# Fri3D_2026_02.net
KiCad netlist of a schematic drawn in Altium Designer
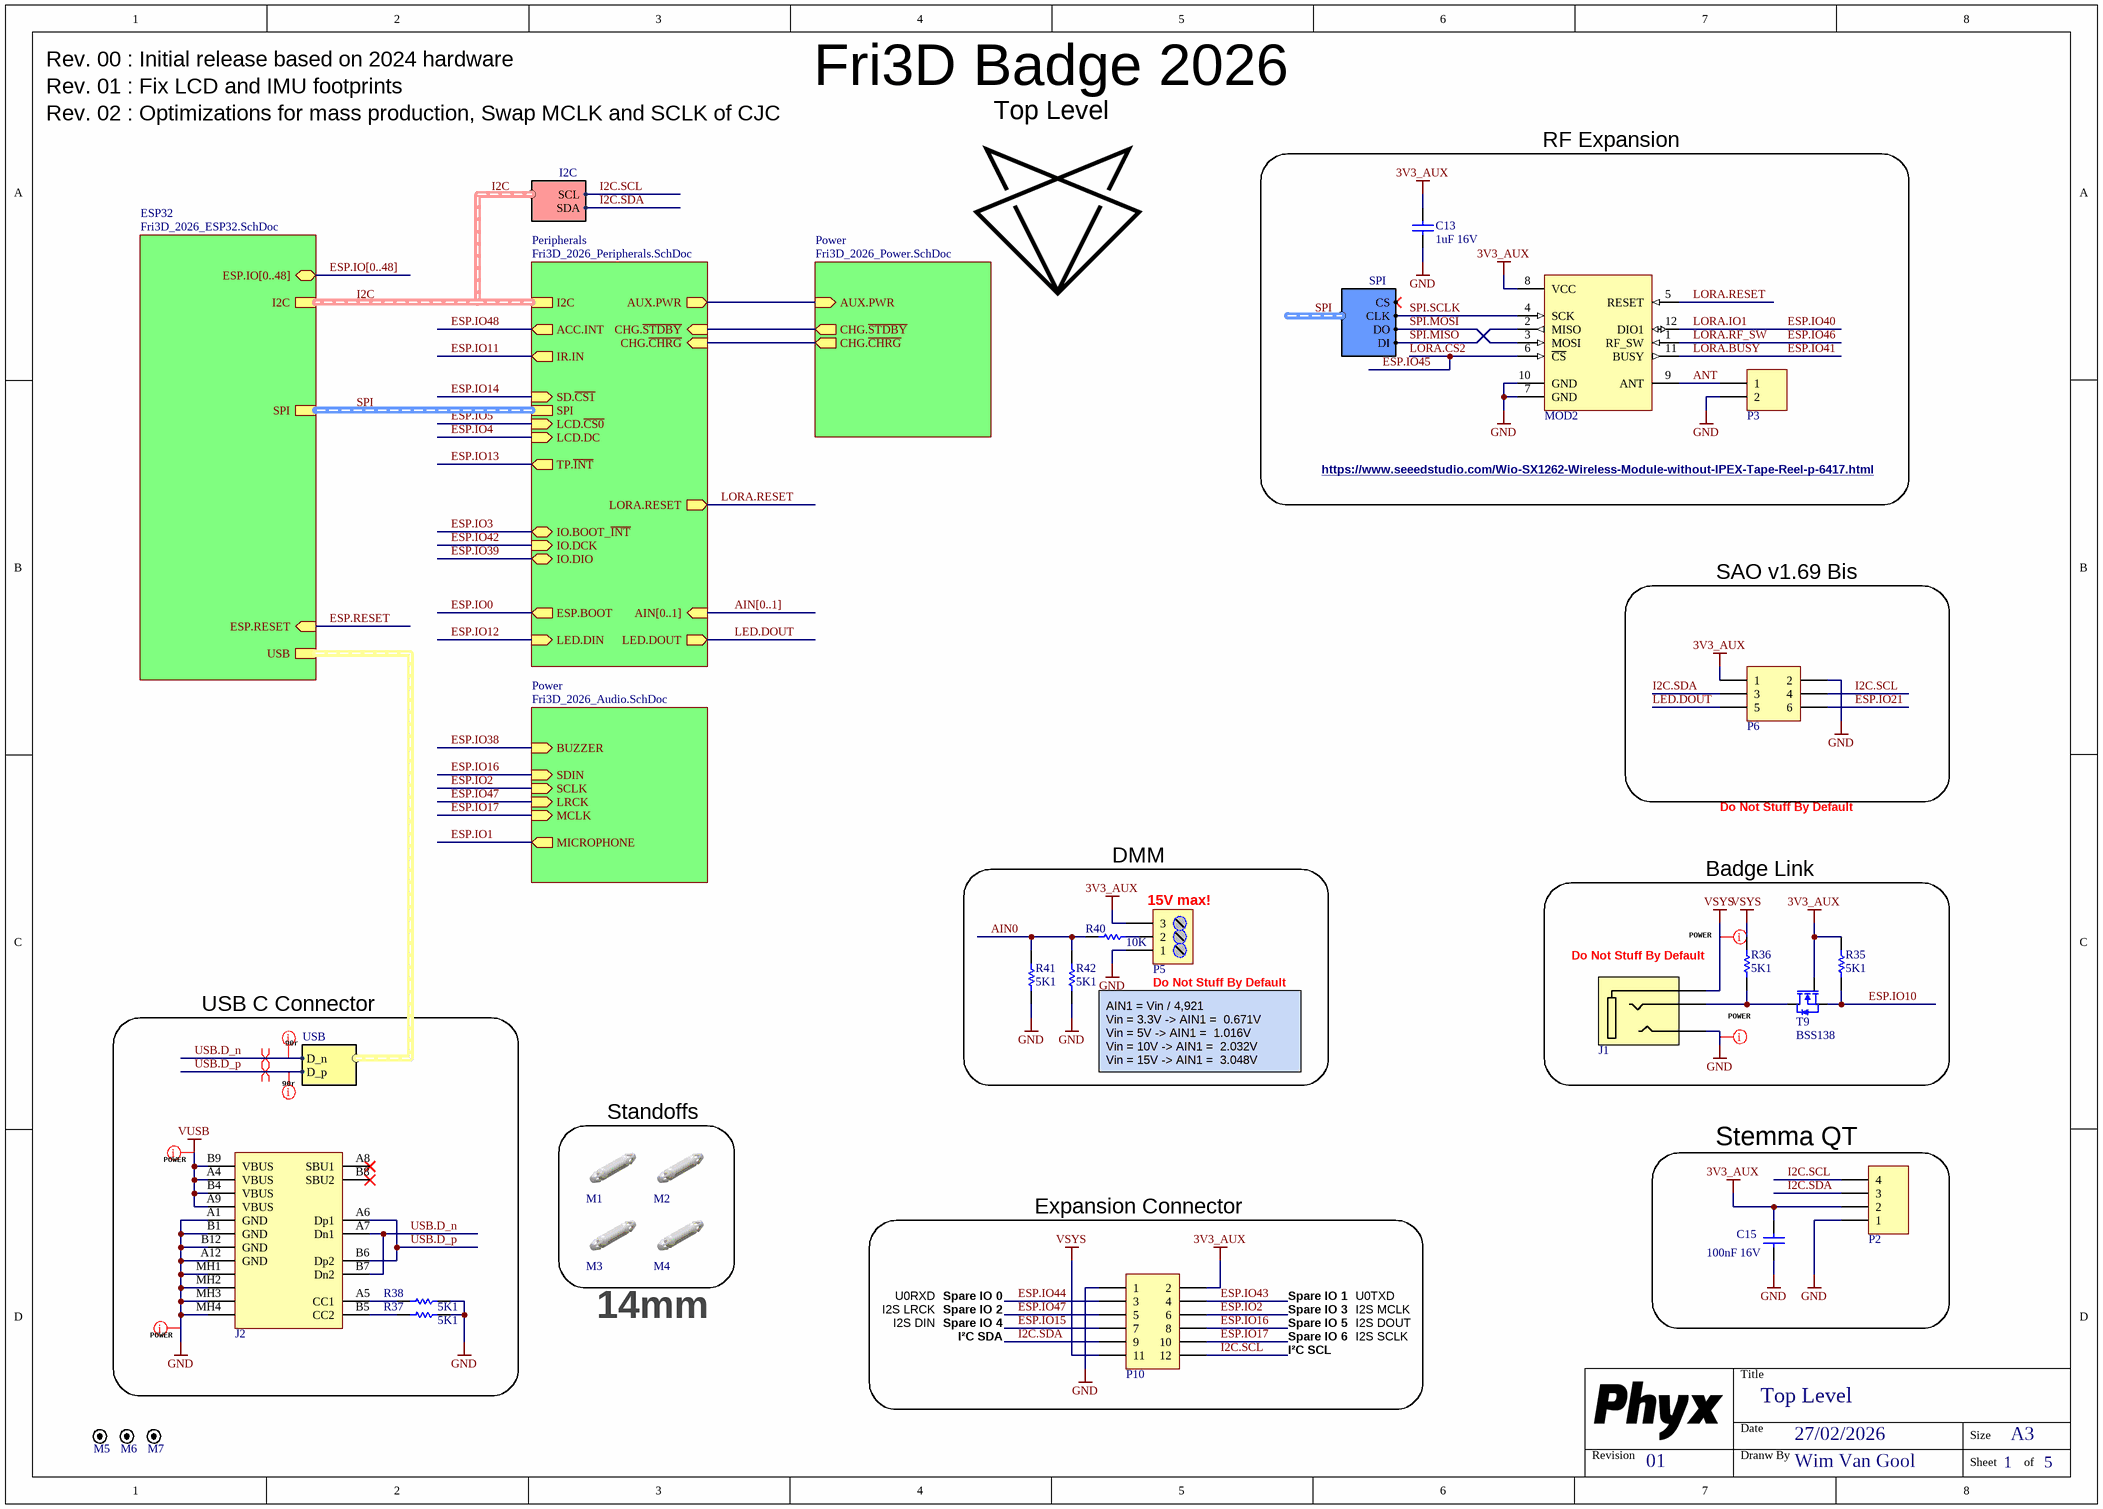
[diagram p0: Fri3D_2026_02.SchDoc]

(export (version "E")
  (design (tool "Eeschema 10.0.6"))
  (components
    (comp (ref "C13")
      (value "1uF 16V")
      (footprint "C0603_N")
      (description "Capacitor Ceramic")
      (libsource (lib "Phyx_Components") (part "CAP_CERAMIC"))
    )
    (comp (ref "C15")
      (value "100nF 16V")
      (footprint "C0603_N")
      (description "Capacitor Ceramic")
      (libsource (lib "Phyx_Components") (part "CAP_CERAMIC"))
    )
    (comp (ref "J1")
      (value "3.5mm jack, black, 3 contacts")
      (footprint "SHOU_HAN_PJ-320A-3P")
      (description "=Description")
      (libsource (lib "Phyx_Components") (part "AUDIO_RST-123"))
    )
    (comp (ref "J2")
      (value "USB 2.0 C Reversible Receptacle Horizontal full SMD")
      (footprint "XUNPU-TYPEC-304S-ACP16")
      (libsource (lib "Phyx_Components") (part "USB_C_16_4"))
    )
    (comp (ref "M1")
      (value "HIWA LCC-12 Snap-in - Snap-in 12.7mm")
      (footprint "WE_709622400")
      (libsource (lib "Phyx_Components") (part "WE_SNSN"))
    )
    (comp (ref "M2")
      (value "HIWA LCC-12 Snap-in - Snap-in 12.7mm")
      (footprint "WE_709622400")
      (libsource (lib "Phyx_Components") (part "WE_SNSN"))
    )
    (comp (ref "M3")
      (value "HIWA LCC-12 Snap-in - Snap-in 12.7mm")
      (footprint "WE_709622400")
      (libsource (lib "Phyx_Components") (part "WE_SNSN"))
    )
    (comp (ref "M4")
      (value "HIWA LCC-12 Snap-in - Snap-in 12.7mm")
      (footprint "WE_709622400")
      (libsource (lib "Phyx_Components") (part "WE_SNSN"))
    )
    (comp (ref "M5")
      (value "Fiducial 0.5mm")
      (footprint "FID_0.5mm")
      (description "FIDUCIAL")
      (libsource (lib "Phyx_Components") (part "FIDUCIAL"))
    )
    (comp (ref "M6")
      (value "Fiducial 0.5mm")
      (footprint "FID_0.5mm")
      (description "FIDUCIAL")
      (libsource (lib "Phyx_Components") (part "FIDUCIAL"))
    )
    (comp (ref "M7")
      (value "Fiducial 0.5mm")
      (footprint "FID_0.5mm")
      (description "FIDUCIAL")
      (libsource (lib "Phyx_Components") (part "FIDUCIAL"))
    )
    (comp (ref "MOD2")
      (value "868/915MHz 22dBm LoRa Module with Antenna Pin")
      (footprint "SEE_Wio-SX1262")
      (description "=Description")
      (libsource (lib "Phyx_Components") (part "SEE_Wio-SX1262"))
    )
    (comp (ref "P2")
      (value "Header 1.0mm RA Shrouded 4")
      (footprint "WE_665104131822")
      (libsource (lib "Phyx_Components") (part "Header 4"))
    )
    (comp (ref "P3")
      (value "DEALON DL-SMA-K513-08K")
      (footprint "DEA_DL-SMA-K513-08K")
      (libsource (lib "Phyx_Components") (part "Header 2"))
    )
    (comp (ref "P5")
      (value "3 Way Screw HDR 3.5mm Rising Cage")
      (footprint "WE_691103110003")
      (libsource (lib "Phyx_Components") (part "TERM_BLCK_3"))
    )
    (comp (ref "P6")
      (value "Receptacle 3x2")
      (footprint "RCPT2X3")
      (libsource (lib "Phyx_Components") (part "Header 3X2"))
    )
    (comp (ref "P10")
      (value "Receptacle 6x2 SMD low profile")
      (footprint "WE_610312243021_POST")
      (libsource (lib "Phyx_Components") (part "Header 6X2"))
    )
    (comp (ref "R35")
      (value "5K1")
      (footprint "R0603_N")
      (libsource (lib "Phyx_Components") (part "RESISTOR"))
    )
    (comp (ref "R36")
      (value "5K1")
      (footprint "R0603_N")
      (libsource (lib "Phyx_Components") (part "RESISTOR"))
    )
    (comp (ref "R37")
      (value "5K1")
      (footprint "R0603_N")
      (libsource (lib "Phyx_Components") (part "RESISTOR"))
    )
    (comp (ref "R38")
      (value "5K1")
      (footprint "R0603_N")
      (libsource (lib "Phyx_Components") (part "RESISTOR"))
    )
    (comp (ref "R40")
      (value "10K")
      (footprint "R0603_N")
      (libsource (lib "Phyx_Components") (part "RESISTOR"))
    )
    (comp (ref "R41")
      (value "5K1")
      (footprint "R0603_N")
      (libsource (lib "Phyx_Components") (part "RESISTOR"))
    )
    (comp (ref "R42")
      (value "5K1")
      (footprint "R0603_N")
      (libsource (lib "Phyx_Components") (part "RESISTOR"))
    )
    (comp (ref "T9")
      (value "BSS138")
      (footprint "SOT23-3")
      (fields (field (name "Comment") "0.2A N-Ch MOSFET Vgs 3.2"))
      (libsource (lib "Phyx_Components") (part "N_MOSFET_GSD"))
    )
  )
  (nets
    (net (code "30") (name "/AIN0") (class "Default")
      (node (ref "R40") (pin "1") (pinfunction "1_1") (pintype "passive"))
      (node (ref "R41") (pin "2") (pinfunction "2_2") (pintype "passive"))
      (node (ref "R42") (pin "2") (pinfunction "2_2") (pintype "passive"))
    )
    (net (code "32") (name "/ANT") (class "Default")
      (node (ref "MOD2") (pin "9") (pinfunction "ANT_9") (pintype "passive"))
      (node (ref "P3") (pin "1") (pinfunction "1_1") (pintype "passive"))
    )
    (net (code "38") (name "/ESP.IO2") (class "Default")
      (node (ref "P10") (pin "6") (pinfunction "6_6") (pintype "passive"))
    )
    (net (code "42") (name "/ESP.IO10") (class "Default")
      (node (ref "R35") (pin "2") (pinfunction "2_2") (pintype "passive"))
      (node (ref "T9") (pin "2") (pinfunction "S_2") (pintype "passive"))
    )
    (net (code "47") (name "/ESP.IO15") (class "Default")
      (node (ref "P10") (pin "7") (pinfunction "7_7") (pintype "passive"))
    )
    (net (code "48") (name "/ESP.IO16") (class "Default")
      (node (ref "P10") (pin "8") (pinfunction "8_8") (pintype "passive"))
    )
    (net (code "49") (name "/ESP.IO17") (class "Default")
      (node (ref "P10") (pin "10") (pinfunction "10_10") (pintype "passive"))
    )
    (net (code "50") (name "/ESP.IO21") (class "Default")
      (node (ref "P6") (pin "6") (pinfunction "6_6") (pintype "passive"))
    )
    (net (code "53") (name "/ESP.IO40") (class "Default")
      (node (ref "MOD2") (pin "12") (pinfunction "DIO1_12") (pintype "bidirectional"))
    )
    (net (code "54") (name "/ESP.IO41") (class "Default")
      (node (ref "MOD2") (pin "11") (pinfunction "BUSY_11") (pintype "output"))
    )
    (net (code "56") (name "/ESP.IO43") (class "Default")
      (node (ref "P10") (pin "4") (pinfunction "4_4") (pintype "passive"))
    )
    (net (code "57") (name "/ESP.IO44") (class "Default")
      (node (ref "P10") (pin "3") (pinfunction "3_3") (pintype "passive"))
    )
    (net (code "58") (name "/ESP.IO45") (class "Default")
      (node (ref "MOD2") (pin "6") (pinfunction "~{CS}_6") (pintype "input"))
    )
    (net (code "59") (name "/ESP.IO46") (class "Default")
      (node (ref "MOD2") (pin "1") (pinfunction "RF_SW_1") (pintype "input"))
    )
    (net (code "60") (name "/ESP.IO47") (class "Default")
      (node (ref "P10") (pin "5") (pinfunction "5_5") (pintype "passive"))
    )
    (net (code "64") (name "/I2C.SCL") (class "Default")
      (node (ref "P10") (pin "12") (pinfunction "12_12") (pintype "passive"))
      (node (ref "P2") (pin "4") (pinfunction "4_4") (pintype "passive"))
      (node (ref "P6") (pin "4") (pinfunction "4_4") (pintype "passive"))
    )
    (net (code "65") (name "/I2C.SDA") (class "Default")
      (node (ref "P10") (pin "9") (pinfunction "9_9") (pintype "passive"))
      (node (ref "P2") (pin "3") (pinfunction "3_3") (pintype "passive"))
      (node (ref "P6") (pin "3") (pinfunction "3_3") (pintype "passive"))
    )
    (net (code "67") (name "/LED.DOUT") (class "Default")
      (node (ref "P6") (pin "5") (pinfunction "5_5") (pintype "passive"))
    )
    (net (code "68") (name "/LORA.RESET") (class "Default")
      (node (ref "MOD2") (pin "5") (pinfunction "RESET_5") (pintype "input"))
    )
    (net (code "69") (name "/SPI.MISO") (class "Default")
      (node (ref "MOD2") (pin "2") (pinfunction "MISO_2") (pintype "output"))
    )
    (net (code "70") (name "/SPI.MOSI") (class "Default")
      (node (ref "MOD2") (pin "3") (pinfunction "MOSI_3") (pintype "input"))
    )
    (net (code "71") (name "/SPI.SCLK") (class "Default")
      (node (ref "MOD2") (pin "4") (pinfunction "SCK_4") (pintype "input"))
    )
    (net (code "73") (name "/USB.D_n") (class "Default")
      (node (ref "J2") (pin "A7") (pinfunction "Dn1_A7") (pintype "passive"))
      (node (ref "J2") (pin "B7") (pinfunction "Dn2_B7") (pintype "passive"))
    )
    (net (code "74") (name "/USB.D_p") (class "Default")
      (node (ref "J2") (pin "A6") (pinfunction "Dp1_A6") (pintype "passive"))
      (node (ref "J2") (pin "B6") (pinfunction "Dp2_B6") (pintype "passive"))
    )
    (net (code "77") (name "3V3_AUX") (class "Default")
      (node (ref "C13") (pin "1") (pinfunction "1_1") (pintype "passive"))
      (node (ref "C15") (pin "1") (pinfunction "1_1") (pintype "passive"))
      (node (ref "MOD2") (pin "8") (pinfunction "VCC_8") (pintype "power_in"))
      (node (ref "P10") (pin "2") (pinfunction "2_2") (pintype "passive"))
      (node (ref "P2") (pin "2") (pinfunction "2_2") (pintype "passive"))
      (node (ref "P5") (pin "3") (pinfunction "3_3") (pintype "passive"))
      (node (ref "P6") (pin "1") (pinfunction "1_1") (pintype "passive"))
      (node (ref "R35") (pin "1") (pinfunction "1_1") (pintype "passive"))
      (node (ref "T9") (pin "1") (pinfunction "G_1") (pintype "passive"))
    )
    (net (code "78") (name "GND") (class "Default")
      (node (ref "C13") (pin "2") (pinfunction "2_2") (pintype "passive"))
      (node (ref "C15") (pin "2") (pinfunction "2_2") (pintype "passive"))
      (node (ref "J1") (pin "2") (pinfunction "Tip_2") (pintype "passive"))
      (node (ref "J2") (pin "A1") (pinfunction "GND_A1") (pintype "passive"))
      (node (ref "J2") (pin "A12") (pinfunction "GND_A12") (pintype "passive"))
      (node (ref "J2") (pin "B1") (pinfunction "GND_B1") (pintype "passive"))
      (node (ref "J2") (pin "B12") (pinfunction "GND_B12") (pintype "passive"))
      (node (ref "J2") (pin "MH1") (pinfunction "Tab_MH1") (pintype "passive"))
      (node (ref "J2") (pin "MH2") (pinfunction "Tab_MH2") (pintype "passive"))
      (node (ref "J2") (pin "MH3") (pinfunction "Tab_MH3") (pintype "passive"))
      (node (ref "J2") (pin "MH4") (pinfunction "Tab_MH4") (pintype "passive"))
      (node (ref "MOD2") (pin "10") (pinfunction "GND_10") (pintype "power_in"))
      (node (ref "MOD2") (pin "7") (pinfunction "GND_7") (pintype "power_in"))
      (node (ref "P10") (pin "1") (pinfunction "1_1") (pintype "passive"))
      (node (ref "P2") (pin "1") (pinfunction "1_1") (pintype "passive"))
      (node (ref "P3") (pin "2") (pinfunction "2_2") (pintype "passive"))
      (node (ref "P5") (pin "1") (pinfunction "1_1") (pintype "passive"))
      (node (ref "P6") (pin "2") (pinfunction "2_2") (pintype "passive"))
      (node (ref "R37") (pin "2") (pinfunction "2_2") (pintype "passive"))
      (node (ref "R38") (pin "2") (pinfunction "2_2") (pintype "passive"))
      (node (ref "R41") (pin "1") (pinfunction "1_1") (pintype "passive"))
      (node (ref "R42") (pin "1") (pinfunction "1_1") (pintype "passive"))
    )
    (net (code "79") (name "Net-(J1-Ring)") (class "Default")
      (node (ref "J1") (pin "3") (pinfunction "Ring_3") (pintype "passive"))
      (node (ref "R36") (pin "2") (pinfunction "2_2") (pintype "passive"))
      (node (ref "T9") (pin "3") (pinfunction "D_3") (pintype "passive"))
    )
    (net (code "80") (name "Net-(J2-CC1)") (class "Default")
      (node (ref "J2") (pin "A5") (pinfunction "CC1_A5") (pintype "passive"))
      (node (ref "R38") (pin "1") (pinfunction "1_1") (pintype "passive"))
    )
    (net (code "81") (name "Net-(J2-CC2)") (class "Default")
      (node (ref "J2") (pin "B5") (pinfunction "CC2_B5") (pintype "passive"))
      (node (ref "R37") (pin "1") (pinfunction "1_1") (pintype "passive"))
    )
    (net (code "82") (name "Net-(P5-Pad2)") (class "Default")
      (node (ref "P5") (pin "2") (pinfunction "2_2") (pintype "passive"))
      (node (ref "R40") (pin "2") (pinfunction "2_2") (pintype "passive"))
    )
    (net (code "83") (name "VSYS") (class "Default")
      (node (ref "J1") (pin "1") (pinfunction "Sleeve_1") (pintype "passive"))
      (node (ref "P10") (pin "11") (pinfunction "11_11") (pintype "passive"))
      (node (ref "R36") (pin "1") (pinfunction "1_1") (pintype "passive"))
    )
    (net (code "84") (name "VUSB") (class "Default")
      (node (ref "J2") (pin "A4") (pinfunction "VBUS_A4") (pintype "passive"))
      (node (ref "J2") (pin "A9") (pinfunction "VBUS_A9") (pintype "passive"))
      (node (ref "J2") (pin "B4") (pinfunction "VBUS_B4") (pintype "passive"))
      (node (ref "J2") (pin "B9") (pinfunction "VBUS_B9") (pintype "passive"))
    )
    (net (code "85") (name "unconnected-(J2-SBU1-PadA8)") (class "Default")
      (node (ref "J2") (pin "A8") (pinfunction "SBU1_A8") (pintype "passive+no_connect"))
    )
    (net (code "86") (name "unconnected-(J2-SBU2-PadB8)") (class "Default")
      (node (ref "J2") (pin "B8") (pinfunction "SBU2_B8") (pintype "passive+no_connect"))
    )
  )
)
